# encoder.net
KiCad netlist of a schematic drawn in Altium Designer
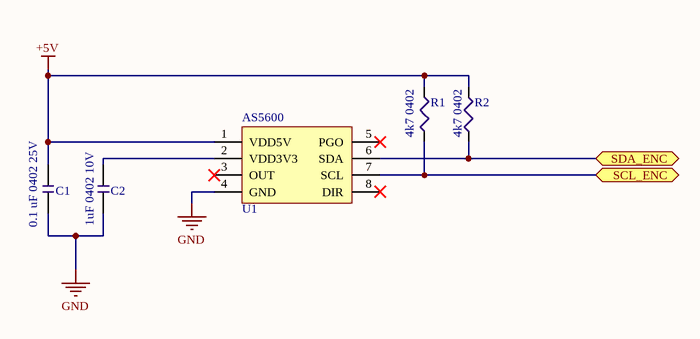
[diagram p0: encoder.SchDoc]

(export (version "E")
  (design (tool "Eeschema 10.0.6"))
  (components
    (comp (ref "C1")
      (value "0.1 uF 0402 25V")
      (footprint "CAP_0402")
      (description "0.1UF 25V 10% X5R 0402")
      (fields (field (name "TOLERANCE") "10%") (field (name "VOLTAGE") "25V"))
      (libsource (lib "ON Development Vault") (part "Capacitor"))
    )
    (comp (ref "C2")
      (value "1uF 0402 10V")
      (footprint "CAP_0402")
      (description "1uF 0402 10V 10% X5R")
      (fields (field (name "TOLERANCE") "10 %") (field (name "VOLTAGE") "10 V"))
      (libsource (lib "ON Development Vault") (part "Capacitor"))
    )
    (comp (ref "R1")
      (value "4k7 0402")
      (footprint "RES_0402")
      (description "RES SMD 4.7K OHM 1% 1/16W 0402")
      (fields (field (name "POWER") "1/16W") (field (name "TOLERANCE") "1"))
      (libsource (lib "ON Development Vault") (part "Resistor"))
    )
    (comp (ref "R2")
      (value "4k7 0402")
      (footprint "RES_0402")
      (description "RES SMD 4.7K OHM 1% 1/16W 0402")
      (fields (field (name "POWER") "1/16W") (field (name "TOLERANCE") "1"))
      (libsource (lib "ON Development Vault") (part "Resistor"))
    )
    (comp (ref "U1")
      (value "AS5600")
      (footprint "AS5600_SOIC8")
      (description "IC SENSOR MAG ROTARY 12BIT 8SOIC")
      (fields (field (name "MFG. PART NUMBER") "AS5600-ASOT"))
      (libsource (lib "ON Development Vault") (part "AS5600"))
    )
  )
  (nets
    (net (code "1") (name "+5V") (class "Default")
      (node (ref "C1") (pin "2") (pinfunction "2_2") (pintype "passive"))
      (node (ref "R1") (pin "2") (pinfunction "2_2") (pintype "passive"))
      (node (ref "R2") (pin "2") (pinfunction "2_2") (pintype "passive"))
      (node (ref "U1") (pin "1") (pinfunction "VDD5V_1") (pintype "passive"))
    )
    (net (code "2") (name "/SCL_ENC") (class "Default")
      (node (ref "R1") (pin "1") (pinfunction "1_1") (pintype "passive"))
      (node (ref "U1") (pin "7") (pinfunction "SCL_7") (pintype "passive"))
    )
    (net (code "3") (name "/SDA_ENC") (class "Default")
      (node (ref "R2") (pin "1") (pinfunction "1_1") (pintype "passive"))
      (node (ref "U1") (pin "6") (pinfunction "SDA_6") (pintype "passive"))
    )
    (net (code "4") (name "GND") (class "Default")
      (node (ref "C1") (pin "1") (pinfunction "1_1") (pintype "passive"))
      (node (ref "C2") (pin "1") (pinfunction "1_1") (pintype "passive"))
      (node (ref "U1") (pin "4") (pinfunction "GND_4") (pintype "passive"))
    )
    (net (code "5") (name "Net-(U1-VDD3V3)") (class "Default")
      (node (ref "C2") (pin "2") (pinfunction "2_2") (pintype "passive"))
      (node (ref "U1") (pin "2") (pinfunction "VDD3V3_2") (pintype "passive"))
    )
    (net (code "6") (name "unconnected-(U1-DIR-Pad8)") (class "Default")
      (node (ref "U1") (pin "8") (pinfunction "DIR_8") (pintype "passive+no_connect"))
    )
    (net (code "7") (name "unconnected-(U1-OUT-Pad3)") (class "Default")
      (node (ref "U1") (pin "3") (pinfunction "OUT_3") (pintype "passive+no_connect"))
    )
    (net (code "8") (name "unconnected-(U1-PGO-Pad5)") (class "Default")
      (node (ref "U1") (pin "5") (pinfunction "PGO_5") (pintype "passive+no_connect"))
    )
  )
)
